# RobotCtrl_Core.net
KiCad netlist of a schematic drawn in Altium Designer
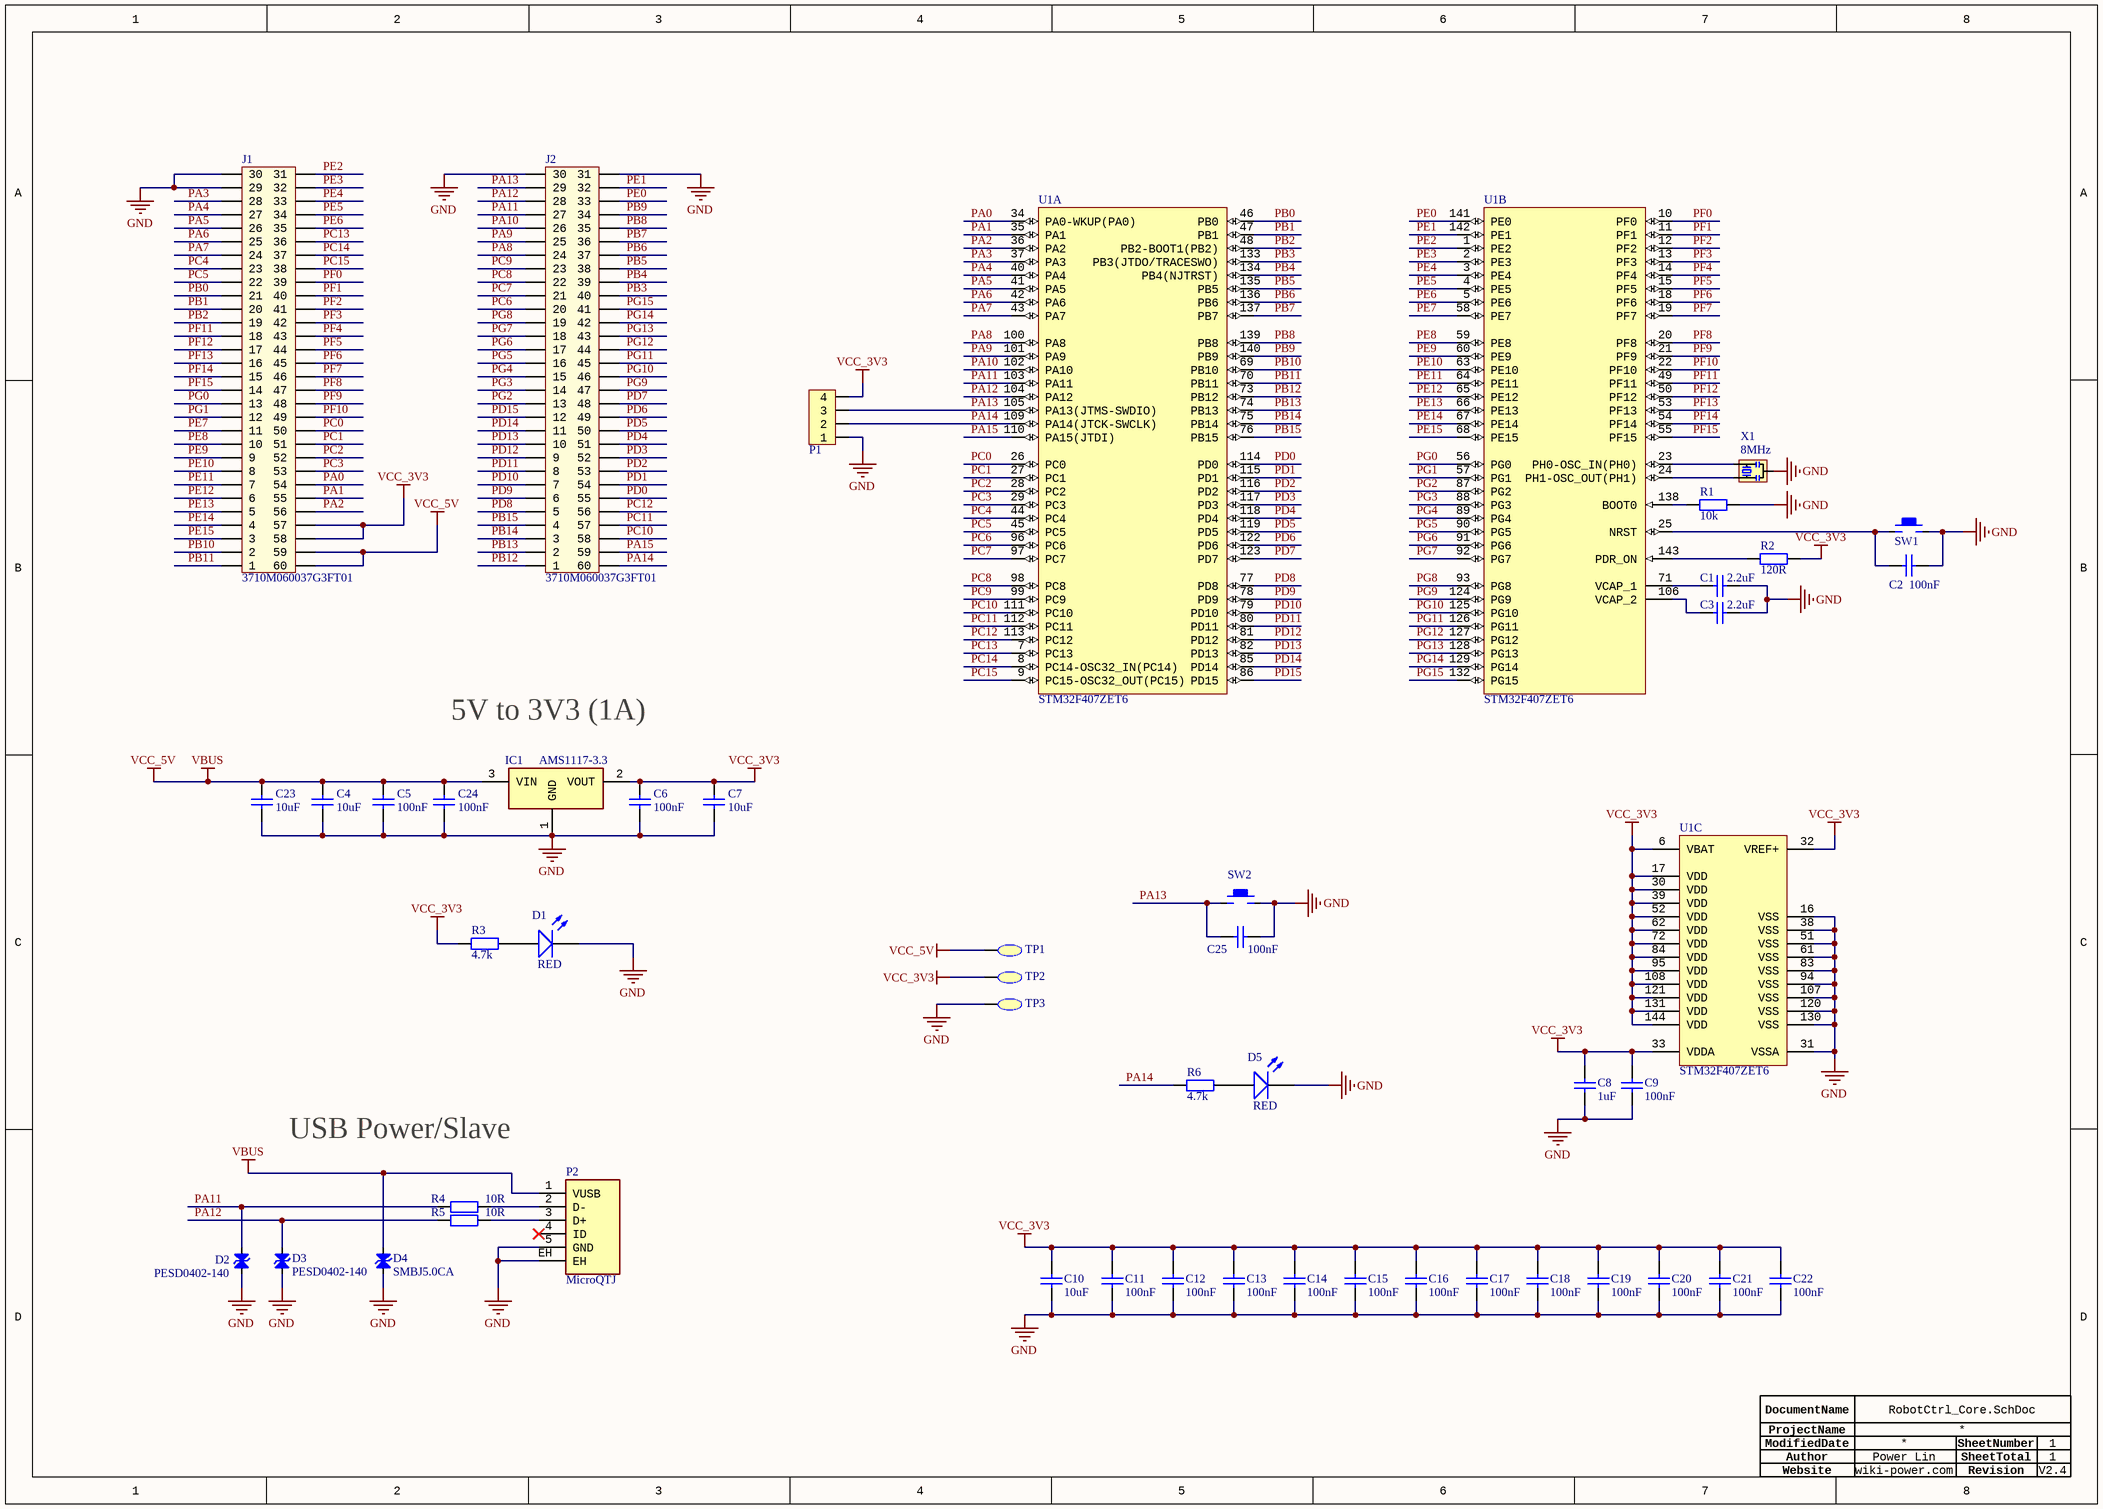
[diagram p0: RobotCtrl_Core.SchDoc]

(export (version "E")
  (design (tool "Eeschema 10.0.6"))
  (components
    (comp (ref "C1")
      (value "2.2uF")
      (footprint "CAP-0603")
      (description "贴片电容")
      (libsource (lib "Power_Lib_Altium") (part "CAP"))
    )
    (comp (ref "C2")
      (value "100nF")
      (footprint "CAP-0603")
      (description "贴片电容")
      (libsource (lib "Power_Lib_Altium") (part "CAP"))
    )
    (comp (ref "C3")
      (value "2.2uF")
      (footprint "CAP-0603")
      (description "贴片电容")
      (libsource (lib "Power_Lib_Altium") (part "CAP"))
    )
    (comp (ref "C4")
      (value "10uF")
      (footprint "CAP-0603")
      (description "贴片电容")
      (libsource (lib "Power_Lib_Altium") (part "CAP"))
    )
    (comp (ref "C5")
      (value "100nF")
      (footprint "CAP-0603")
      (description "贴片电容")
      (libsource (lib "Power_Lib_Altium") (part "CAP"))
    )
    (comp (ref "C6")
      (value "100nF")
      (footprint "CAP-0603")
      (description "贴片电容")
      (libsource (lib "Power_Lib_Altium") (part "CAP"))
    )
    (comp (ref "C7")
      (value "10uF")
      (footprint "CAP-0603")
      (description "贴片电容")
      (libsource (lib "Power_Lib_Altium") (part "CAP"))
    )
    (comp (ref "C8")
      (value "1uF")
      (footprint "CAP-0402")
      (description "贴片电容")
      (libsource (lib "Power_Lib_Altium") (part "CAP"))
    )
    (comp (ref "C9")
      (value "100nF")
      (footprint "CAP-0402")
      (description "贴片电容")
      (libsource (lib "Power_Lib_Altium") (part "CAP"))
    )
    (comp (ref "C10")
      (value "10uF")
      (footprint "CAP-0402")
      (description "贴片电容")
      (libsource (lib "Power_Lib_Altium") (part "CAP"))
    )
    (comp (ref "C11")
      (value "100nF")
      (footprint "CAP-0402")
      (description "贴片电容")
      (libsource (lib "Power_Lib_Altium") (part "CAP"))
    )
    (comp (ref "C12")
      (value "100nF")
      (footprint "CAP-0402")
      (description "贴片电容")
      (libsource (lib "Power_Lib_Altium") (part "CAP"))
    )
    (comp (ref "C13")
      (value "100nF")
      (footprint "CAP-0402")
      (description "贴片电容")
      (libsource (lib "Power_Lib_Altium") (part "CAP"))
    )
    (comp (ref "C14")
      (value "100nF")
      (footprint "CAP-0402")
      (description "贴片电容")
      (libsource (lib "Power_Lib_Altium") (part "CAP"))
    )
    (comp (ref "C15")
      (value "100nF")
      (footprint "CAP-0402")
      (description "贴片电容")
      (libsource (lib "Power_Lib_Altium") (part "CAP"))
    )
    (comp (ref "C16")
      (value "100nF")
      (footprint "CAP-0402")
      (description "贴片电容")
      (libsource (lib "Power_Lib_Altium") (part "CAP"))
    )
    (comp (ref "C17")
      (value "100nF")
      (footprint "CAP-0402")
      (description "贴片电容")
      (libsource (lib "Power_Lib_Altium") (part "CAP"))
    )
    (comp (ref "C18")
      (value "100nF")
      (footprint "CAP-0402")
      (description "贴片电容")
      (libsource (lib "Power_Lib_Altium") (part "CAP"))
    )
    (comp (ref "C19")
      (value "100nF")
      (footprint "CAP-0402")
      (description "贴片电容")
      (libsource (lib "Power_Lib_Altium") (part "CAP"))
    )
    (comp (ref "C20")
      (value "100nF")
      (footprint "CAP-0402")
      (description "贴片电容")
      (libsource (lib "Power_Lib_Altium") (part "CAP"))
    )
    (comp (ref "C21")
      (value "100nF")
      (footprint "CAP-0402")
      (description "贴片电容")
      (libsource (lib "Power_Lib_Altium") (part "CAP"))
    )
    (comp (ref "C22")
      (value "100nF")
      (footprint "CAP-0402")
      (description "贴片电容")
      (libsource (lib "Power_Lib_Altium") (part "CAP"))
    )
    (comp (ref "C23")
      (value "10uF")
      (footprint "CAP-0603")
      (description "贴片电容")
      (libsource (lib "Power_Lib_Altium") (part "CAP"))
    )
    (comp (ref "C24")
      (value "100nF")
      (footprint "CAP-0603")
      (description "贴片电容")
      (libsource (lib "Power_Lib_Altium") (part "CAP"))
    )
    (comp (ref "C25")
      (value "100nF")
      (footprint "CAP-0603")
      (description "贴片电容")
      (libsource (lib "Power_Lib_Altium") (part "CAP"))
    )
    (comp (ref "D1")
      (value "RED")
      (footprint "LED-0603")
      (description "发光二极管")
      (libsource (lib "Power_Lib_Altium") (part "LED"))
    )
    (comp (ref "D2")
      (value "PESD0402-140")
      (footprint "D-0402")
      (libsource (lib "Power_Lib_Altium") (part "TVS_C"))
    )
    (comp (ref "D3")
      (value "PESD0402-140")
      (footprint "D-0402")
      (libsource (lib "Power_Lib_Altium") (part "TVS_C"))
    )
    (comp (ref "D4")
      (value "SMBJ5.0CA")
      (footprint "DO-214AA/SMB")
      (description "Brightking / MDD")
      (libsource (lib "Power_Lib_Altium") (part "TVS_C"))
    )
    (comp (ref "D5")
      (value "RED")
      (footprint "LED-0603")
      (description "发光二极管")
      (libsource (lib "Power_Lib_Altium") (part "LED"))
    )
    (comp (ref "IC1")
      (value "AMS1117-3.3")
      (footprint "SOT-223")
      (description "AMS1117-3.3 1.0A")
      (fields (field (name "MANUFACTURER_PART_NUMBER") "SI2302DS") (field (name "RS PART NUMBER") "7983053P"))
      (libsource (lib "Power_Lib_Altium") (part "AMS1117"))
    )
    (comp (ref "J1")
      (value "3710M060037G3FT01")
      (footprint "3710M060037G3FT01")
      (description "B2B Connector")
      (libsource (lib "Power_Lib_Altium") (part "3710M/F"))
    )
    (comp (ref "J2")
      (value "3710M060037G3FT01")
      (footprint "3710M060037G3FT01")
      (description "B2B Connector")
      (libsource (lib "Power_Lib_Altium") (part "3710M/F"))
    )
    (comp (ref "P1")
      (value "HDR1x4_2.54")
      (footprint "HDR1X4_2.54")
      (description "Header")
      (libsource (lib "Power_Lib_Altium") (part "HDR1x4_2.54"))
    )
    (comp (ref "P2")
      (value "MicroQTJ")
      (footprint "USB-MICRO")
      (description "USB_MICRO")
      (libsource (lib "Power_Lib_Altium") (part "USB_MICRO"))
    )
    (comp (ref "R1")
      (value "10k")
      (footprint "R-0603")
      (description "贴片电阻")
      (libsource (lib "Power_Lib_Altium") (part "RES"))
    )
    (comp (ref "R2")
      (value "120R")
      (footprint "R-0603")
      (description "贴片电阻")
      (libsource (lib "Power_Lib_Altium") (part "RES"))
    )
    (comp (ref "R3")
      (value "4.7k")
      (footprint "R-0603")
      (description "贴片电阻")
      (libsource (lib "Power_Lib_Altium") (part "RES"))
    )
    (comp (ref "R4")
      (value "10R")
      (footprint "R-0603")
      (description "贴片电阻")
      (libsource (lib "") (part "RES_1"))
    )
    (comp (ref "R5")
      (value "10R")
      (footprint "R-0603")
      (description "贴片电阻")
      (libsource (lib "") (part "RES_1"))
    )
    (comp (ref "R6")
      (value "4.7k")
      (footprint "R-0603")
      (description "贴片电阻")
      (libsource (lib "Power_Lib_Altium") (part "RES"))
    )
    (comp (ref "SW1")
      (value "KEY")
      (footprint "KEY-4P-4.2*3.4*2.5")
      (description "按键开关")
      (libsource (lib "Power_Lib_Altium") (part "KEY"))
    )
    (comp (ref "SW2")
      (value "KEY")
      (footprint "KEY-4P-4.2*3.4*2.5")
      (description "按键开关")
      (libsource (lib "Power_Lib_Altium") (part "KEY"))
    )
    (comp (ref "TP1")
      (value "TestPoint")
      (footprint "TestPoint")
      (description "测试点")
      (libsource (lib "Power_Lib_Altium") (part "TestPoint"))
    )
    (comp (ref "TP2")
      (value "TestPoint")
      (footprint "TestPoint")
      (description "测试点")
      (libsource (lib "Power_Lib_Altium") (part "TestPoint"))
    )
    (comp (ref "TP3")
      (value "TestPoint")
      (footprint "TestPoint")
      (description "测试点")
      (libsource (lib "Power_Lib_Altium") (part "TestPoint"))
    )
    (comp (ref "U1")
      (value "STM32F407ZET6")
      (footprint "STM-LQFP144_N")
      (fields (field (name "MANUFACTURER") "STMicroelectronics"))
      (libsource (lib "Power_Lib_Altium") (part "STM32F407ZET6"))
    )
    (comp (ref "X1")
      (value "8MHz")
      (footprint "SMD3213-3P")
      (description "CSTCE8M00G15C99-R0")
      (libsource (lib "Power_Lib_Altium") (part "XTAL"))
    )
  )
  (nets
    (net (code "1") (name "/PA0") (class "Default")
      (node (ref "J1") (pin "54") (pinfunction "54_54") (pintype "passive"))
      (node (ref "U1") (pin "34") (pinfunction "PA0-WKUP(PA0)_34") (pintype "bidirectional"))
    )
    (net (code "2") (name "/PA1") (class "Default")
      (node (ref "J1") (pin "55") (pinfunction "55_55") (pintype "passive"))
      (node (ref "U1") (pin "35") (pinfunction "PA1_35") (pintype "bidirectional"))
    )
    (net (code "3") (name "/PA2") (class "Default")
      (node (ref "J1") (pin "56") (pinfunction "56_56") (pintype "passive"))
      (node (ref "U1") (pin "36") (pinfunction "PA2_36") (pintype "bidirectional"))
    )
    (net (code "4") (name "/PA3") (class "Default")
      (node (ref "J1") (pin "28") (pinfunction "28_28") (pintype "passive"))
      (node (ref "U1") (pin "37") (pinfunction "PA3_37") (pintype "bidirectional"))
    )
    (net (code "5") (name "/PA4") (class "Default")
      (node (ref "J1") (pin "27") (pinfunction "27_27") (pintype "passive"))
      (node (ref "U1") (pin "40") (pinfunction "PA4_40") (pintype "bidirectional"))
    )
    (net (code "6") (name "/PA5") (class "Default")
      (node (ref "J1") (pin "26") (pinfunction "26_26") (pintype "passive"))
      (node (ref "U1") (pin "41") (pinfunction "PA5_41") (pintype "bidirectional"))
    )
    (net (code "7") (name "/PA6") (class "Default")
      (node (ref "J1") (pin "25") (pinfunction "25_25") (pintype "passive"))
      (node (ref "U1") (pin "42") (pinfunction "PA6_42") (pintype "bidirectional"))
    )
    (net (code "8") (name "/PA7") (class "Default")
      (node (ref "J1") (pin "24") (pinfunction "24_24") (pintype "passive"))
      (node (ref "U1") (pin "43") (pinfunction "PA7_43") (pintype "bidirectional"))
    )
    (net (code "9") (name "/PA8") (class "Default")
      (node (ref "J2") (pin "24") (pinfunction "24_24") (pintype "passive"))
      (node (ref "U1") (pin "100") (pinfunction "PA8_100") (pintype "bidirectional"))
    )
    (net (code "10") (name "/PA9") (class "Default")
      (node (ref "J2") (pin "25") (pinfunction "25_25") (pintype "passive"))
      (node (ref "U1") (pin "101") (pinfunction "PA9_101") (pintype "bidirectional"))
    )
    (net (code "11") (name "/PA10") (class "Default")
      (node (ref "J2") (pin "26") (pinfunction "26_26") (pintype "passive"))
      (node (ref "U1") (pin "102") (pinfunction "PA10_102") (pintype "bidirectional"))
    )
    (net (code "12") (name "/PA11") (class "Default")
      (node (ref "D2") (pin "2") (pinfunction "2_2") (pintype "passive"))
      (node (ref "J2") (pin "27") (pinfunction "27_27") (pintype "passive"))
      (node (ref "R4") (pin "1") (pinfunction "1_1") (pintype "passive"))
      (node (ref "U1") (pin "103") (pinfunction "PA11_103") (pintype "bidirectional"))
    )
    (net (code "13") (name "/PA12") (class "Default")
      (node (ref "D3") (pin "2") (pinfunction "2_2") (pintype "passive"))
      (node (ref "J2") (pin "28") (pinfunction "28_28") (pintype "passive"))
      (node (ref "R5") (pin "1") (pinfunction "1_1") (pintype "passive"))
      (node (ref "U1") (pin "104") (pinfunction "PA12_104") (pintype "bidirectional"))
    )
    (net (code "14") (name "/PA13") (class "Default")
      (node (ref "C25") (pin "2") (pinfunction "2_2") (pintype "passive"))
      (node (ref "J2") (pin "29") (pinfunction "29_29") (pintype "passive"))
      (node (ref "P1") (pin "3") (pinfunction "3_3") (pintype "passive"))
      (node (ref "SW2") (pin "1") (pinfunction "1_1") (pintype "passive"))
      (node (ref "U1") (pin "105") (pinfunction "PA13(JTMS-SWDIO)_105") (pintype "bidirectional"))
    )
    (net (code "15") (name "/PA14") (class "Default")
      (node (ref "J2") (pin "60") (pinfunction "60_60") (pintype "passive"))
      (node (ref "P1") (pin "2") (pinfunction "2_2") (pintype "passive"))
      (node (ref "R6") (pin "2") (pinfunction "2_2") (pintype "passive"))
      (node (ref "U1") (pin "109") (pinfunction "PA14(JTCK-SWCLK)_109") (pintype "bidirectional"))
    )
    (net (code "16") (name "/PA15") (class "Default")
      (node (ref "J2") (pin "59") (pinfunction "59_59") (pintype "passive"))
      (node (ref "U1") (pin "110") (pinfunction "PA15(JTDI)_110") (pintype "bidirectional"))
    )
    (net (code "17") (name "/PB0") (class "Default")
      (node (ref "J1") (pin "21") (pinfunction "21_21") (pintype "passive"))
      (node (ref "U1") (pin "46") (pinfunction "PB0_46") (pintype "bidirectional"))
    )
    (net (code "18") (name "/PB1") (class "Default")
      (node (ref "J1") (pin "20") (pinfunction "20_20") (pintype "passive"))
      (node (ref "U1") (pin "47") (pinfunction "PB1_47") (pintype "bidirectional"))
    )
    (net (code "19") (name "/PB2") (class "Default")
      (node (ref "J1") (pin "19") (pinfunction "19_19") (pintype "passive"))
      (node (ref "U1") (pin "48") (pinfunction "PB2-BOOT1(PB2)_48") (pintype "bidirectional"))
    )
    (net (code "20") (name "/PB3") (class "Default")
      (node (ref "J2") (pin "40") (pinfunction "40_40") (pintype "passive"))
      (node (ref "U1") (pin "133") (pinfunction "PB3(JTDO/TRACESWO)_133") (pintype "bidirectional"))
    )
    (net (code "21") (name "/PB4") (class "Default")
      (node (ref "J2") (pin "39") (pinfunction "39_39") (pintype "passive"))
      (node (ref "U1") (pin "134") (pinfunction "PB4(NJTRST)_134") (pintype "bidirectional"))
    )
    (net (code "22") (name "/PB5") (class "Default")
      (node (ref "J2") (pin "38") (pinfunction "38_38") (pintype "passive"))
      (node (ref "U1") (pin "135") (pinfunction "PB5_135") (pintype "bidirectional"))
    )
    (net (code "23") (name "/PB6") (class "Default")
      (node (ref "J2") (pin "37") (pinfunction "37_37") (pintype "passive"))
      (node (ref "U1") (pin "136") (pinfunction "PB6_136") (pintype "bidirectional"))
    )
    (net (code "24") (name "/PB7") (class "Default")
      (node (ref "J2") (pin "36") (pinfunction "36_36") (pintype "passive"))
      (node (ref "U1") (pin "137") (pinfunction "PB7_137") (pintype "bidirectional"))
    )
    (net (code "25") (name "/PB8") (class "Default")
      (node (ref "J2") (pin "35") (pinfunction "35_35") (pintype "passive"))
      (node (ref "U1") (pin "139") (pinfunction "PB8_139") (pintype "bidirectional"))
    )
    (net (code "26") (name "/PB9") (class "Default")
      (node (ref "J2") (pin "34") (pinfunction "34_34") (pintype "passive"))
      (node (ref "U1") (pin "140") (pinfunction "PB9_140") (pintype "bidirectional"))
    )
    (net (code "27") (name "/PB10") (class "Default")
      (node (ref "J1") (pin "2") (pinfunction "2_2") (pintype "passive"))
      (node (ref "U1") (pin "69") (pinfunction "PB10_69") (pintype "bidirectional"))
    )
    (net (code "28") (name "/PB11") (class "Default")
      (node (ref "J1") (pin "1") (pinfunction "1_1") (pintype "passive"))
      (node (ref "U1") (pin "70") (pinfunction "PB11_70") (pintype "bidirectional"))
    )
    (net (code "29") (name "/PB12") (class "Default")
      (node (ref "J2") (pin "1") (pinfunction "1_1") (pintype "passive"))
      (node (ref "U1") (pin "73") (pinfunction "PB12_73") (pintype "bidirectional"))
    )
    (net (code "30") (name "/PB13") (class "Default")
      (node (ref "J2") (pin "2") (pinfunction "2_2") (pintype "passive"))
      (node (ref "U1") (pin "74") (pinfunction "PB13_74") (pintype "bidirectional"))
    )
    (net (code "31") (name "/PB14") (class "Default")
      (node (ref "J2") (pin "3") (pinfunction "3_3") (pintype "passive"))
      (node (ref "U1") (pin "75") (pinfunction "PB14_75") (pintype "bidirectional"))
    )
    (net (code "32") (name "/PB15") (class "Default")
      (node (ref "J2") (pin "4") (pinfunction "4_4") (pintype "passive"))
      (node (ref "U1") (pin "76") (pinfunction "PB15_76") (pintype "bidirectional"))
    )
    (net (code "33") (name "/PC0") (class "Default")
      (node (ref "J1") (pin "50") (pinfunction "50_50") (pintype "passive"))
      (node (ref "U1") (pin "26") (pinfunction "PC0_26") (pintype "bidirectional"))
    )
    (net (code "34") (name "/PC1") (class "Default")
      (node (ref "J1") (pin "51") (pinfunction "51_51") (pintype "passive"))
      (node (ref "U1") (pin "27") (pinfunction "PC1_27") (pintype "bidirectional"))
    )
    (net (code "35") (name "/PC2") (class "Default")
      (node (ref "J1") (pin "52") (pinfunction "52_52") (pintype "passive"))
      (node (ref "U1") (pin "28") (pinfunction "PC2_28") (pintype "bidirectional"))
    )
    (net (code "36") (name "/PC3") (class "Default")
      (node (ref "J1") (pin "53") (pinfunction "53_53") (pintype "passive"))
      (node (ref "U1") (pin "29") (pinfunction "PC3_29") (pintype "bidirectional"))
    )
    (net (code "37") (name "/PC4") (class "Default")
      (node (ref "J1") (pin "23") (pinfunction "23_23") (pintype "passive"))
      (node (ref "U1") (pin "44") (pinfunction "PC4_44") (pintype "bidirectional"))
    )
    (net (code "38") (name "/PC5") (class "Default")
      (node (ref "J1") (pin "22") (pinfunction "22_22") (pintype "passive"))
      (node (ref "U1") (pin "45") (pinfunction "PC5_45") (pintype "bidirectional"))
    )
    (net (code "39") (name "/PC6") (class "Default")
      (node (ref "J2") (pin "20") (pinfunction "20_20") (pintype "passive"))
      (node (ref "U1") (pin "96") (pinfunction "PC6_96") (pintype "bidirectional"))
    )
    (net (code "40") (name "/PC7") (class "Default")
      (node (ref "J2") (pin "21") (pinfunction "21_21") (pintype "passive"))
      (node (ref "U1") (pin "97") (pinfunction "PC7_97") (pintype "bidirectional"))
    )
    (net (code "41") (name "/PC8") (class "Default")
      (node (ref "J2") (pin "22") (pinfunction "22_22") (pintype "passive"))
      (node (ref "U1") (pin "98") (pinfunction "PC8_98") (pintype "bidirectional"))
    )
    (net (code "42") (name "/PC9") (class "Default")
      (node (ref "J2") (pin "23") (pinfunction "23_23") (pintype "passive"))
      (node (ref "U1") (pin "99") (pinfunction "PC9_99") (pintype "bidirectional"))
    )
    (net (code "43") (name "/PC10") (class "Default")
      (node (ref "J2") (pin "58") (pinfunction "58_58") (pintype "passive"))
      (node (ref "U1") (pin "111") (pinfunction "PC10_111") (pintype "bidirectional"))
    )
    (net (code "44") (name "/PC11") (class "Default")
      (node (ref "J2") (pin "57") (pinfunction "57_57") (pintype "passive"))
      (node (ref "U1") (pin "112") (pinfunction "PC11_112") (pintype "bidirectional"))
    )
    (net (code "45") (name "/PC12") (class "Default")
      (node (ref "J2") (pin "56") (pinfunction "56_56") (pintype "passive"))
      (node (ref "U1") (pin "113") (pinfunction "PC12_113") (pintype "bidirectional"))
    )
    (net (code "46") (name "/PC13") (class "Default")
      (node (ref "J1") (pin "36") (pinfunction "36_36") (pintype "passive"))
      (node (ref "U1") (pin "7") (pinfunction "PC13_7") (pintype "bidirectional"))
    )
    (net (code "47") (name "/PC14") (class "Default")
      (node (ref "J1") (pin "37") (pinfunction "37_37") (pintype "passive"))
      (node (ref "U1") (pin "8") (pinfunction "PC14-OSC32_IN(PC14)_8") (pintype "bidirectional"))
    )
    (net (code "48") (name "/PC15") (class "Default")
      (node (ref "J1") (pin "38") (pinfunction "38_38") (pintype "passive"))
      (node (ref "U1") (pin "9") (pinfunction "PC15-OSC32_OUT(PC15)_9") (pintype "bidirectional"))
    )
    (net (code "49") (name "/PD0") (class "Default")
      (node (ref "J2") (pin "55") (pinfunction "55_55") (pintype "passive"))
      (node (ref "U1") (pin "114") (pinfunction "PD0_114") (pintype "bidirectional"))
    )
    (net (code "50") (name "/PD1") (class "Default")
      (node (ref "J2") (pin "54") (pinfunction "54_54") (pintype "passive"))
      (node (ref "U1") (pin "115") (pinfunction "PD1_115") (pintype "bidirectional"))
    )
    (net (code "51") (name "/PD2") (class "Default")
      (node (ref "J2") (pin "53") (pinfunction "53_53") (pintype "passive"))
      (node (ref "U1") (pin "116") (pinfunction "PD2_116") (pintype "bidirectional"))
    )
    (net (code "52") (name "/PD3") (class "Default")
      (node (ref "J2") (pin "52") (pinfunction "52_52") (pintype "passive"))
      (node (ref "U1") (pin "117") (pinfunction "PD3_117") (pintype "bidirectional"))
    )
    (net (code "53") (name "/PD4") (class "Default")
      (node (ref "J2") (pin "51") (pinfunction "51_51") (pintype "passive"))
      (node (ref "U1") (pin "118") (pinfunction "PD4_118") (pintype "bidirectional"))
    )
    (net (code "54") (name "/PD5") (class "Default")
      (node (ref "J2") (pin "50") (pinfunction "50_50") (pintype "passive"))
      (node (ref "U1") (pin "119") (pinfunction "PD5_119") (pintype "bidirectional"))
    )
    (net (code "55") (name "/PD6") (class "Default")
      (node (ref "J2") (pin "49") (pinfunction "49_49") (pintype "passive"))
      (node (ref "U1") (pin "122") (pinfunction "PD6_122") (pintype "bidirectional"))
    )
    (net (code "56") (name "/PD7") (class "Default")
      (node (ref "J2") (pin "48") (pinfunction "48_48") (pintype "passive"))
      (node (ref "U1") (pin "123") (pinfunction "PD7_123") (pintype "bidirectional"))
    )
    (net (code "57") (name "/PD8") (class "Default")
      (node (ref "J2") (pin "5") (pinfunction "5_5") (pintype "passive"))
      (node (ref "U1") (pin "77") (pinfunction "PD8_77") (pintype "bidirectional"))
    )
    (net (code "58") (name "/PD9") (class "Default")
      (node (ref "J2") (pin "6") (pinfunction "6_6") (pintype "passive"))
      (node (ref "U1") (pin "78") (pinfunction "PD9_78") (pintype "bidirectional"))
    )
    (net (code "59") (name "/PD10") (class "Default")
      (node (ref "J2") (pin "7") (pinfunction "7_7") (pintype "passive"))
      (node (ref "U1") (pin "79") (pinfunction "PD10_79") (pintype "bidirectional"))
    )
    (net (code "60") (name "/PD11") (class "Default")
      (node (ref "J2") (pin "8") (pinfunction "8_8") (pintype "passive"))
      (node (ref "U1") (pin "80") (pinfunction "PD11_80") (pintype "bidirectional"))
    )
    (net (code "61") (name "/PD12") (class "Default")
      (node (ref "J2") (pin "9") (pinfunction "9_9") (pintype "passive"))
      (node (ref "U1") (pin "81") (pinfunction "PD12_81") (pintype "bidirectional"))
    )
    (net (code "62") (name "/PD13") (class "Default")
      (node (ref "J2") (pin "10") (pinfunction "10_10") (pintype "passive"))
      (node (ref "U1") (pin "82") (pinfunction "PD13_82") (pintype "bidirectional"))
    )
    (net (code "63") (name "/PD14") (class "Default")
      (node (ref "J2") (pin "11") (pinfunction "11_11") (pintype "passive"))
      (node (ref "U1") (pin "85") (pinfunction "PD14_85") (pintype "bidirectional"))
    )
    (net (code "64") (name "/PD15") (class "Default")
      (node (ref "J2") (pin "12") (pinfunction "12_12") (pintype "passive"))
      (node (ref "U1") (pin "86") (pinfunction "PD15_86") (pintype "bidirectional"))
    )
    (net (code "65") (name "/PE0") (class "Default")
      (node (ref "J2") (pin "33") (pinfunction "33_33") (pintype "passive"))
      (node (ref "U1") (pin "141") (pinfunction "PE0_141") (pintype "bidirectional"))
    )
    (net (code "66") (name "/PE1") (class "Default")
      (node (ref "J2") (pin "32") (pinfunction "32_32") (pintype "passive"))
      (node (ref "U1") (pin "142") (pinfunction "PE1_142") (pintype "bidirectional"))
    )
    (net (code "67") (name "/PE2") (class "Default")
      (node (ref "J1") (pin "31") (pinfunction "31_31") (pintype "passive"))
      (node (ref "U1") (pin "1") (pinfunction "PE2_1") (pintype "bidirectional"))
    )
    (net (code "68") (name "/PE3") (class "Default")
      (node (ref "J1") (pin "32") (pinfunction "32_32") (pintype "passive"))
      (node (ref "U1") (pin "2") (pinfunction "PE3_2") (pintype "bidirectional"))
    )
    (net (code "69") (name "/PE4") (class "Default")
      (node (ref "J1") (pin "33") (pinfunction "33_33") (pintype "passive"))
      (node (ref "U1") (pin "3") (pinfunction "PE4_3") (pintype "bidirectional"))
    )
    (net (code "70") (name "/PE5") (class "Default")
      (node (ref "J1") (pin "34") (pinfunction "34_34") (pintype "passive"))
      (node (ref "U1") (pin "4") (pinfunction "PE5_4") (pintype "bidirectional"))
    )
    (net (code "71") (name "/PE6") (class "Default")
      (node (ref "J1") (pin "35") (pinfunction "35_35") (pintype "passive"))
      (node (ref "U1") (pin "5") (pinfunction "PE6_5") (pintype "bidirectional"))
    )
    (net (code "72") (name "/PE7") (class "Default")
      (node (ref "J1") (pin "11") (pinfunction "11_11") (pintype "passive"))
      (node (ref "U1") (pin "58") (pinfunction "PE7_58") (pintype "bidirectional"))
    )
    (net (code "73") (name "/PE8") (class "Default")
      (node (ref "J1") (pin "10") (pinfunction "10_10") (pintype "passive"))
      (node (ref "U1") (pin "59") (pinfunction "PE8_59") (pintype "bidirectional"))
    )
    (net (code "74") (name "/PE9") (class "Default")
      (node (ref "J1") (pin "9") (pinfunction "9_9") (pintype "passive"))
      (node (ref "U1") (pin "60") (pinfunction "PE9_60") (pintype "bidirectional"))
    )
    (net (code "75") (name "/PE10") (class "Default")
      (node (ref "J1") (pin "8") (pinfunction "8_8") (pintype "passive"))
      (node (ref "U1") (pin "63") (pinfunction "PE10_63") (pintype "bidirectional"))
    )
    (net (code "76") (name "/PE11") (class "Default")
      (node (ref "J1") (pin "7") (pinfunction "7_7") (pintype "passive"))
      (node (ref "U1") (pin "64") (pinfunction "PE11_64") (pintype "bidirectional"))
    )
    (net (code "77") (name "/PE12") (class "Default")
      (node (ref "J1") (pin "6") (pinfunction "6_6") (pintype "passive"))
      (node (ref "U1") (pin "65") (pinfunction "PE12_65") (pintype "bidirectional"))
    )
    (net (code "78") (name "/PE13") (class "Default")
      (node (ref "J1") (pin "5") (pinfunction "5_5") (pintype "passive"))
      (node (ref "U1") (pin "66") (pinfunction "PE13_66") (pintype "bidirectional"))
    )
    (net (code "79") (name "/PE14") (class "Default")
      (node (ref "J1") (pin "4") (pinfunction "4_4") (pintype "passive"))
      (node (ref "U1") (pin "67") (pinfunction "PE14_67") (pintype "bidirectional"))
    )
    (net (code "80") (name "/PE15") (class "Default")
      (node (ref "J1") (pin "3") (pinfunction "3_3") (pintype "passive"))
      (node (ref "U1") (pin "68") (pinfunction "PE15_68") (pintype "bidirectional"))
    )
    (net (code "81") (name "/PF0") (class "Default")
      (node (ref "J1") (pin "39") (pinfunction "39_39") (pintype "passive"))
      (node (ref "U1") (pin "10") (pinfunction "PF0_10") (pintype "bidirectional"))
    )
    (net (code "82") (name "/PF1") (class "Default")
      (node (ref "J1") (pin "40") (pinfunction "40_40") (pintype "passive"))
      (node (ref "U1") (pin "11") (pinfunction "PF1_11") (pintype "bidirectional"))
    )
    (net (code "83") (name "/PF2") (class "Default")
      (node (ref "J1") (pin "41") (pinfunction "41_41") (pintype "passive"))
      (node (ref "U1") (pin "12") (pinfunction "PF2_12") (pintype "bidirectional"))
    )
    (net (code "84") (name "/PF3") (class "Default")
      (node (ref "J1") (pin "42") (pinfunction "42_42") (pintype "passive"))
      (node (ref "U1") (pin "13") (pinfunction "PF3_13") (pintype "bidirectional"))
    )
    (net (code "85") (name "/PF4") (class "Default")
      (node (ref "J1") (pin "43") (pinfunction "43_43") (pintype "passive"))
      (node (ref "U1") (pin "14") (pinfunction "PF4_14") (pintype "bidirectional"))
    )
    (net (code "86") (name "/PF5") (class "Default")
      (node (ref "J1") (pin "44") (pinfunction "44_44") (pintype "passive"))
      (node (ref "U1") (pin "15") (pinfunction "PF5_15") (pintype "bidirectional"))
    )
    (net (code "87") (name "/PF6") (class "Default")
      (node (ref "J1") (pin "45") (pinfunction "45_45") (pintype "passive"))
      (node (ref "U1") (pin "18") (pinfunction "PF6_18") (pintype "bidirectional"))
    )
    (net (code "88") (name "/PF7") (class "Default")
      (node (ref "J1") (pin "46") (pinfunction "46_46") (pintype "passive"))
      (node (ref "U1") (pin "19") (pinfunction "PF7_19") (pintype "bidirectional"))
    )
    (net (code "89") (name "/PF8") (class "Default")
      (node (ref "J1") (pin "47") (pinfunction "47_47") (pintype "passive"))
      (node (ref "U1") (pin "20") (pinfunction "PF8_20") (pintype "bidirectional"))
    )
    (net (code "90") (name "/PF9") (class "Default")
      (node (ref "J1") (pin "48") (pinfunction "48_48") (pintype "passive"))
      (node (ref "U1") (pin "21") (pinfunction "PF9_21") (pintype "bidirectional"))
    )
    (net (code "91") (name "/PF10") (class "Default")
      (node (ref "J1") (pin "49") (pinfunction "49_49") (pintype "passive"))
      (node (ref "U1") (pin "22") (pinfunction "PF10_22") (pintype "bidirectional"))
    )
    (net (code "92") (name "/PF11") (class "Default")
      (node (ref "J1") (pin "18") (pinfunction "18_18") (pintype "passive"))
      (node (ref "U1") (pin "49") (pinfunction "PF11_49") (pintype "bidirectional"))
    )
    (net (code "93") (name "/PF12") (class "Default")
      (node (ref "J1") (pin "17") (pinfunction "17_17") (pintype "passive"))
      (node (ref "U1") (pin "50") (pinfunction "PF12_50") (pintype "bidirectional"))
    )
    (net (code "94") (name "/PF13") (class "Default")
      (node (ref "J1") (pin "16") (pinfunction "16_16") (pintype "passive"))
      (node (ref "U1") (pin "53") (pinfunction "PF13_53") (pintype "bidirectional"))
    )
    (net (code "95") (name "/PF14") (class "Default")
      (node (ref "J1") (pin "15") (pinfunction "15_15") (pintype "passive"))
      (node (ref "U1") (pin "54") (pinfunction "PF14_54") (pintype "bidirectional"))
    )
    (net (code "96") (name "/PF15") (class "Default")
      (node (ref "J1") (pin "14") (pinfunction "14_14") (pintype "passive"))
      (node (ref "U1") (pin "55") (pinfunction "PF15_55") (pintype "bidirectional"))
    )
    (net (code "97") (name "/PG0") (class "Default")
      (node (ref "J1") (pin "13") (pinfunction "13_13") (pintype "passive"))
      (node (ref "U1") (pin "56") (pinfunction "PG0_56") (pintype "bidirectional"))
    )
    (net (code "98") (name "/PG1") (class "Default")
      (node (ref "J1") (pin "12") (pinfunction "12_12") (pintype "passive"))
      (node (ref "U1") (pin "57") (pinfunction "PG1_57") (pintype "bidirectional"))
    )
    (net (code "99") (name "/PG2") (class "Default")
      (node (ref "J2") (pin "13") (pinfunction "13_13") (pintype "passive"))
      (node (ref "U1") (pin "87") (pinfunction "PG2_87") (pintype "bidirectional"))
    )
    (net (code "100") (name "/PG3") (class "Default")
      (node (ref "J2") (pin "14") (pinfunction "14_14") (pintype "passive"))
      (node (ref "U1") (pin "88") (pinfunction "PG3_88") (pintype "bidirectional"))
    )
    (net (code "101") (name "/PG4") (class "Default")
      (node (ref "J2") (pin "15") (pinfunction "15_15") (pintype "passive"))
      (node (ref "U1") (pin "89") (pinfunction "PG4_89") (pintype "bidirectional"))
    )
    (net (code "102") (name "/PG5") (class "Default")
      (node (ref "J2") (pin "16") (pinfunction "16_16") (pintype "passive"))
      (node (ref "U1") (pin "90") (pinfunction "PG5_90") (pintype "bidirectional"))
    )
    (net (code "103") (name "/PG6") (class "Default")
      (node (ref "J2") (pin "17") (pinfunction "17_17") (pintype "passive"))
      (node (ref "U1") (pin "91") (pinfunction "PG6_91") (pintype "bidirectional"))
    )
    (net (code "104") (name "/PG7") (class "Default")
      (node (ref "J2") (pin "18") (pinfunction "18_18") (pintype "passive"))
      (node (ref "U1") (pin "92") (pinfunction "PG7_92") (pintype "bidirectional"))
    )
    (net (code "105") (name "/PG8") (class "Default")
      (node (ref "J2") (pin "19") (pinfunction "19_19") (pintype "passive"))
      (node (ref "U1") (pin "93") (pinfunction "PG8_93") (pintype "bidirectional"))
    )
    (net (code "106") (name "/PG9") (class "Default")
      (node (ref "J2") (pin "47") (pinfunction "47_47") (pintype "passive"))
      (node (ref "U1") (pin "124") (pinfunction "PG9_124") (pintype "bidirectional"))
    )
    (net (code "107") (name "/PG10") (class "Default")
      (node (ref "J2") (pin "46") (pinfunction "46_46") (pintype "passive"))
      (node (ref "U1") (pin "125") (pinfunction "PG10_125") (pintype "bidirectional"))
    )
    (net (code "108") (name "/PG11") (class "Default")
      (node (ref "J2") (pin "45") (pinfunction "45_45") (pintype "passive"))
      (node (ref "U1") (pin "126") (pinfunction "PG11_126") (pintype "bidirectional"))
    )
    (net (code "109") (name "/PG12") (class "Default")
      (node (ref "J2") (pin "44") (pinfunction "44_44") (pintype "passive"))
      (node (ref "U1") (pin "127") (pinfunction "PG12_127") (pintype "bidirectional"))
    )
    (net (code "110") (name "/PG13") (class "Default")
      (node (ref "J2") (pin "43") (pinfunction "43_43") (pintype "passive"))
      (node (ref "U1") (pin "128") (pinfunction "PG13_128") (pintype "bidirectional"))
    )
    (net (code "111") (name "/PG14") (class "Default")
      (node (ref "J2") (pin "42") (pinfunction "42_42") (pintype "passive"))
      (node (ref "U1") (pin "129") (pinfunction "PG14_129") (pintype "bidirectional"))
    )
    (net (code "112") (name "/PG15") (class "Default")
      (node (ref "J2") (pin "41") (pinfunction "41_41") (pintype "passive"))
      (node (ref "U1") (pin "132") (pinfunction "PG15_132") (pintype "bidirectional"))
    )
    (net (code "113") (name "GND") (class "Default")
      (node (ref "C1") (pin "2") (pinfunction "2_2") (pintype "passive"))
      (node (ref "C10") (pin "1") (pinfunction "1_1") (pintype "passive"))
      (node (ref "C11") (pin "1") (pinfunction "1_1") (pintype "passive"))
      (node (ref "C12") (pin "1") (pinfunction "1_1") (pintype "passive"))
      (node (ref "C13") (pin "1") (pinfunction "1_1") (pintype "passive"))
      (node (ref "C14") (pin "1") (pinfunction "1_1") (pintype "passive"))
      (node (ref "C15") (pin "1") (pinfunction "1_1") (pintype "passive"))
      (node (ref "C16") (pin "1") (pinfunction "1_1") (pintype "passive"))
      (node (ref "C17") (pin "1") (pinfunction "1_1") (pintype "passive"))
      (node (ref "C18") (pin "1") (pinfunction "1_1") (pintype "passive"))
      (node (ref "C19") (pin "1") (pinfunction "1_1") (pintype "passive"))
      (node (ref "C2") (pin "1") (pinfunction "1_1") (pintype "passive"))
      (node (ref "C20") (pin "1") (pinfunction "1_1") (pintype "passive"))
      (node (ref "C21") (pin "1") (pinfunction "1_1") (pintype "passive"))
      (node (ref "C22") (pin "1") (pinfunction "1_1") (pintype "passive"))
      (node (ref "C23") (pin "1") (pinfunction "1_1") (pintype "passive"))
      (node (ref "C24") (pin "1") (pinfunction "1_1") (pintype "passive"))
      (node (ref "C25") (pin "1") (pinfunction "1_1") (pintype "passive"))
      (node (ref "C3") (pin "2") (pinfunction "2_2") (pintype "passive"))
      (node (ref "C4") (pin "1") (pinfunction "1_1") (pintype "passive"))
      (node (ref "C5") (pin "1") (pinfunction "1_1") (pintype "passive"))
      (node (ref "C6") (pin "1") (pinfunction "1_1") (pintype "passive"))
      (node (ref "C7") (pin "1") (pinfunction "1_1") (pintype "passive"))
      (node (ref "C8") (pin "1") (pinfunction "1_1") (pintype "passive"))
      (node (ref "C9") (pin "1") (pinfunction "1_1") (pintype "passive"))
      (node (ref "D1") (pin "K") (pinfunction "K_K") (pintype "passive"))
      (node (ref "D2") (pin "1") (pinfunction "1_1") (pintype "passive"))
      (node (ref "D3") (pin "1") (pinfunction "1_1") (pintype "passive"))
      (node (ref "D4") (pin "1") (pinfunction "1_1") (pintype "passive"))
      (node (ref "D5") (pin "K") (pinfunction "K_K") (pintype "passive"))
      (node (ref "IC1") (pin "1") (pinfunction "GND_1") (pintype "passive"))
      (node (ref "J1") (pin "29") (pinfunction "29_29") (pintype "passive"))
      (node (ref "J1") (pin "30") (pinfunction "30_30") (pintype "passive"))
      (node (ref "J2") (pin "30") (pinfunction "30_30") (pintype "passive"))
      (node (ref "J2") (pin "31") (pinfunction "31_31") (pintype "passive"))
      (node (ref "P1") (pin "1") (pinfunction "1_1") (pintype "passive"))
      (node (ref "P2") (pin "5") (pinfunction "GND_5") (pintype "passive"))
      (node (ref "P2") (pin "EH") (pinfunction "EH_EH") (pintype "passive"))
      (node (ref "R1") (pin "1") (pinfunction "1_1") (pintype "passive"))
      (node (ref "SW1") (pin "2") (pinfunction "2_2") (pintype "passive"))
      (node (ref "SW2") (pin "2") (pinfunction "2_2") (pintype "passive"))
      (node (ref "TP3") (pin "1") (pinfunction "1_1") (pintype "passive"))
      (node (ref "U1") (pin "107") (pinfunction "VSS_107") (pintype "power_in"))
      (node (ref "U1") (pin "120") (pinfunction "VSS_120") (pintype "power_in"))
      (node (ref "U1") (pin "130") (pinfunction "VSS_130") (pintype "power_in"))
      (node (ref "U1") (pin "16") (pinfunction "VSS_16") (pintype "power_in"))
      (node (ref "U1") (pin "31") (pinfunction "VSSA_31") (pintype "power_in"))
      (node (ref "U1") (pin "38") (pinfunction "VSS_38") (pintype "power_in"))
      (node (ref "U1") (pin "51") (pinfunction "VSS_51") (pintype "power_in"))
      (node (ref "U1") (pin "61") (pinfunction "VSS_61") (pintype "power_in"))
      (node (ref "U1") (pin "83") (pinfunction "VSS_83") (pintype "power_in"))
      (node (ref "U1") (pin "94") (pinfunction "VSS_94") (pintype "power_in"))
      (node (ref "X1") (pin "2") (pinfunction "GND_2") (pintype "passive"))
    )
    (net (code "114") (name "Net-(D1-PadA)") (class "Default")
      (node (ref "D1") (pin "A") (pinfunction "A_A") (pintype "passive"))
      (node (ref "R3") (pin "1") (pinfunction "1_1") (pintype "passive"))
    )
    (net (code "115") (name "Net-(D5-PadA)") (class "Default")
      (node (ref "D5") (pin "A") (pinfunction "A_A") (pintype "passive"))
      (node (ref "R6") (pin "1") (pinfunction "1_1") (pintype "passive"))
    )
    (net (code "116") (name "Net-(P2-D+)") (class "Default")
      (node (ref "P2") (pin "3") (pinfunction "D+_3") (pintype "passive"))
      (node (ref "R5") (pin "2") (pinfunction "2_2") (pintype "passive"))
    )
    (net (code "117") (name "Net-(P2-D-)") (class "Default")
      (node (ref "P2") (pin "2") (pinfunction "D-_2") (pintype "passive"))
      (node (ref "R4") (pin "2") (pinfunction "2_2") (pintype "passive"))
    )
    (net (code "118") (name "Net-(U1B-BOOT0)") (class "Default")
      (node (ref "R1") (pin "2") (pinfunction "2_2") (pintype "passive"))
      (node (ref "U1") (pin "138") (pinfunction "BOOT0_138") (pintype "input"))
    )
    (net (code "119") (name "Net-(U1B-NRST)") (class "Default")
      (node (ref "C2") (pin "2") (pinfunction "2_2") (pintype "passive"))
      (node (ref "SW1") (pin "1") (pinfunction "1_1") (pintype "passive"))
      (node (ref "U1") (pin "25") (pinfunction "NRST_25") (pintype "bidirectional"))
    )
    (net (code "120") (name "Net-(U1B-PDR_ON)") (class "Default")
      (node (ref "R2") (pin "2") (pinfunction "2_2") (pintype "passive"))
      (node (ref "U1") (pin "143") (pinfunction "PDR_ON_143") (pintype "input"))
    )
    (net (code "121") (name "Net-(U1B-PH0-OSC_IN(PH0))") (class "Default")
      (node (ref "U1") (pin "23") (pinfunction "PH0-OSC_IN(PH0)_23") (pintype "bidirectional"))
      (node (ref "X1") (pin "3") (pinfunction "OSC2_3") (pintype "passive"))
    )
    (net (code "122") (name "Net-(U1B-PH1-OSC_OUT(PH1))") (class "Default")
      (node (ref "U1") (pin "24") (pinfunction "PH1-OSC_OUT(PH1)_24") (pintype "bidirectional"))
      (node (ref "X1") (pin "1") (pinfunction "OSC1_1") (pintype "passive"))
    )
    (net (code "123") (name "Net-(U1B-VCAP_1)") (class "Default")
      (node (ref "C1") (pin "1") (pinfunction "1_1") (pintype "passive"))
      (node (ref "U1") (pin "71") (pinfunction "VCAP_1_71") (pintype "power_in"))
    )
    (net (code "124") (name "Net-(U1B-VCAP_2)") (class "Default")
      (node (ref "C3") (pin "1") (pinfunction "1_1") (pintype "passive"))
      (node (ref "U1") (pin "106") (pinfunction "VCAP_2_106") (pintype "power_in"))
    )
    (net (code "125") (name "VBUS") (class "Default")
      (node (ref "C23") (pin "2") (pinfunction "2_2") (pintype "passive"))
      (node (ref "C24") (pin "2") (pinfunction "2_2") (pintype "passive"))
      (node (ref "C4") (pin "2") (pinfunction "2_2") (pintype "passive"))
      (node (ref "C5") (pin "2") (pinfunction "2_2") (pintype "passive"))
      (node (ref "D4") (pin "2") (pinfunction "2_2") (pintype "passive"))
      (node (ref "IC1") (pin "3") (pinfunction "VIN_3") (pintype "passive"))
      (node (ref "J1") (pin "59") (pinfunction "59_59") (pintype "passive"))
      (node (ref "J1") (pin "60") (pinfunction "60_60") (pintype "passive"))
      (node (ref "P2") (pin "1") (pinfunction "VUSB_1") (pintype "passive"))
      (node (ref "TP1") (pin "1") (pinfunction "1_1") (pintype "passive"))
    )
    (net (code "126") (name "VCC_3V3") (class "Default")
      (node (ref "C10") (pin "2") (pinfunction "2_2") (pintype "passive"))
      (node (ref "C11") (pin "2") (pinfunction "2_2") (pintype "passive"))
      (node (ref "C12") (pin "2") (pinfunction "2_2") (pintype "passive"))
      (node (ref "C13") (pin "2") (pinfunction "2_2") (pintype "passive"))
      (node (ref "C14") (pin "2") (pinfunction "2_2") (pintype "passive"))
      (node (ref "C15") (pin "2") (pinfunction "2_2") (pintype "passive"))
      (node (ref "C16") (pin "2") (pinfunction "2_2") (pintype "passive"))
      (node (ref "C17") (pin "2") (pinfunction "2_2") (pintype "passive"))
      (node (ref "C18") (pin "2") (pinfunction "2_2") (pintype "passive"))
      (node (ref "C19") (pin "2") (pinfunction "2_2") (pintype "passive"))
      (node (ref "C20") (pin "2") (pinfunction "2_2") (pintype "passive"))
      (node (ref "C21") (pin "2") (pinfunction "2_2") (pintype "passive"))
      (node (ref "C22") (pin "2") (pinfunction "2_2") (pintype "passive"))
      (node (ref "C6") (pin "2") (pinfunction "2_2") (pintype "passive"))
      (node (ref "C7") (pin "2") (pinfunction "2_2") (pintype "passive"))
      (node (ref "C8") (pin "2") (pinfunction "2_2") (pintype "passive"))
      (node (ref "C9") (pin "2") (pinfunction "2_2") (pintype "passive"))
      (node (ref "IC1") (pin "2") (pinfunction "VOUT_2") (pintype "passive"))
      (node (ref "J1") (pin "57") (pinfunction "57_57") (pintype "passive"))
      (node (ref "J1") (pin "58") (pinfunction "58_58") (pintype "passive"))
      (node (ref "P1") (pin "4") (pinfunction "4_4") (pintype "passive"))
      (node (ref "R2") (pin "1") (pinfunction "1_1") (pintype "passive"))
      (node (ref "R3") (pin "2") (pinfunction "2_2") (pintype "passive"))
      (node (ref "TP2") (pin "1") (pinfunction "1_1") (pintype "passive"))
      (node (ref "U1") (pin "108") (pinfunction "VDD_108") (pintype "power_in"))
      (node (ref "U1") (pin "121") (pinfunction "VDD_121") (pintype "power_in"))
      (node (ref "U1") (pin "131") (pinfunction "VDD_131") (pintype "power_in"))
      (node (ref "U1") (pin "144") (pinfunction "VDD_144") (pintype "power_in"))
      (node (ref "U1") (pin "17") (pinfunction "VDD_17") (pintype "power_in"))
      (node (ref "U1") (pin "30") (pinfunction "VDD_30") (pintype "power_in"))
      (node (ref "U1") (pin "32") (pinfunction "VREF+_32") (pintype "power_in"))
      (node (ref "U1") (pin "33") (pinfunction "VDDA_33") (pintype "power_in"))
      (node (ref "U1") (pin "39") (pinfunction "VDD_39") (pintype "power_in"))
      (node (ref "U1") (pin "52") (pinfunction "VDD_52") (pintype "power_in"))
      (node (ref "U1") (pin "6") (pinfunction "VBAT_6") (pintype "power_in"))
      (node (ref "U1") (pin "62") (pinfunction "VDD_62") (pintype "power_in"))
      (node (ref "U1") (pin "72") (pinfunction "VDD_72") (pintype "power_in"))
      (node (ref "U1") (pin "84") (pinfunction "VDD_84") (pintype "power_in"))
      (node (ref "U1") (pin "95") (pinfunction "VDD_95") (pintype "power_in"))
    )
    (net (code "127") (name "unconnected-(P2-ID-Pad4)") (class "Default")
      (node (ref "P2") (pin "4") (pinfunction "ID_4") (pintype "passive+no_connect"))
    )
  )
)
